# Sheet1.net
KiCad netlist of a schematic drawn in Altium Designer
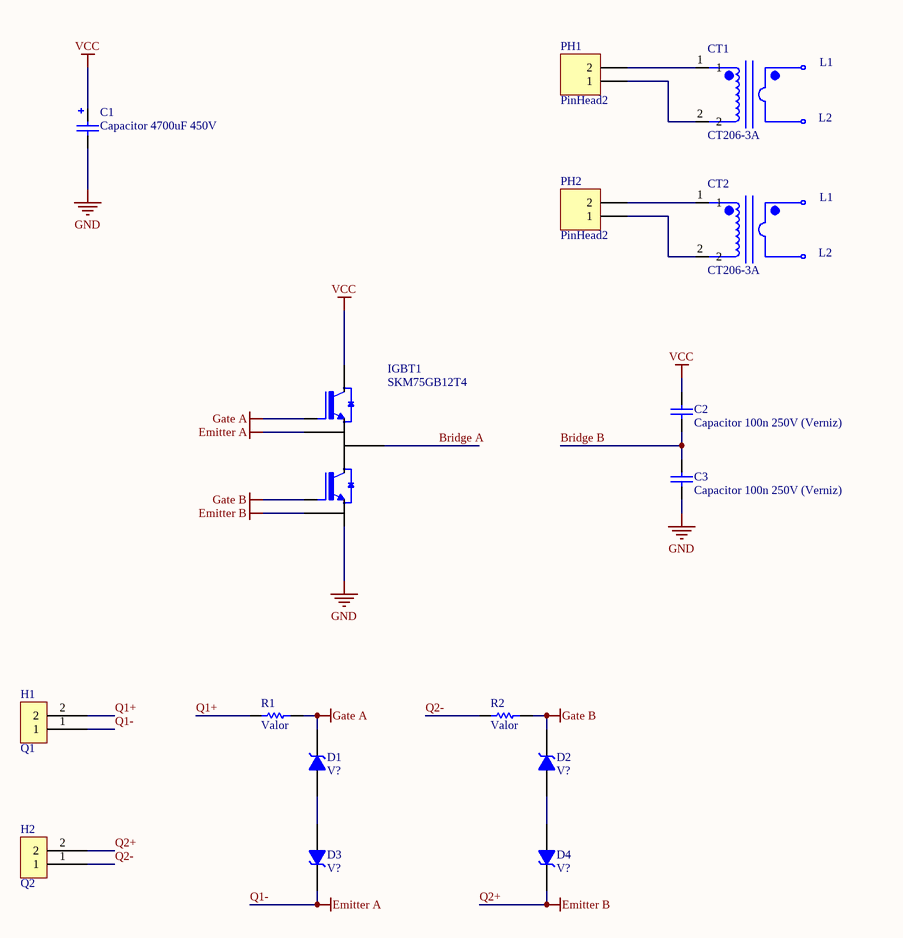
[diagram p0: Sheet1.SchDoc]

(export (version "E")
  (design (tool "Eeschema 10.0.6"))
  (components
    (comp (ref "C1")
      (value "Capacitor 4700uF 450V")
      (footprint "Capacitor 4700uF 450V RIFA")
      (libsource (lib "SPaivachlib1") (part "Capacitor 4700uF 450V"))
    )
    (comp (ref "C2")
      (value "Capacitor 100n 250V (Verniz)")
      (footprint "Capacitor 100n (cor verniz)")
      (libsource (lib "SPaivachlib1") (part "Capacitor 100n 250V (Verniz)"))
    )
    (comp (ref "C3")
      (value "Capacitor 100n 250V (Verniz)")
      (footprint "Capacitor 100n (cor verniz)")
      (libsource (lib "SPaivachlib1") (part "Capacitor 100n 250V (Verniz)"))
    )
    (comp (ref "CT1")
      (value "CT206-3A")
      (footprint "CT206-3A")
      (description "PTH Current Transformer")
      (libsource (lib "SPaivachlib1") (part "CT206-3A"))
    )
    (comp (ref "CT2")
      (value "CT206-3A")
      (footprint "CT206-3A")
      (description "PTH Current Transformer")
      (libsource (lib "SPaivachlib1") (part "CT206-3A"))
    )
    (comp (ref "D1")
      (value "V?")
      (footprint "SOD-80")
      (description "Diodo zener")
      (libsource (lib "LIB_Ampera_2021 (1)") (part "Zener"))
    )
    (comp (ref "D2")
      (value "V?")
      (footprint "SOD-80")
      (description "Diodo zener")
      (libsource (lib "LIB_Ampera_2021 (1)") (part "Zener"))
    )
    (comp (ref "D3")
      (value "V?")
      (footprint "SOD-80")
      (description "Diodo zener")
      (libsource (lib "LIB_Ampera_2021 (1)") (part "Zener"))
    )
    (comp (ref "D4")
      (value "V?")
      (footprint "SOD-80")
      (description "Diodo zener")
      (libsource (lib "LIB_Ampera_2021 (1)") (part "Zener"))
    )
    (comp (ref "H1")
      (value "Q1")
      (footprint "Pin Socket 1x2 TH Pitch 2.54mm")
      (description "Socket to header connector with 2 pins")
      (libsource (lib "LIB_Ampera_2021 (1)") (part "HEADER_SOCKET_2"))
    )
    (comp (ref "H2")
      (value "Q2")
      (footprint "Pin Socket 1x2 TH Pitch 2.54mm")
      (description "Socket to header connector with 2 pins")
      (libsource (lib "LIB_Ampera_2021 (1)") (part "HEADER_SOCKET_2"))
    )
    (comp (ref "IGBT1")
      (value "SKM75GB12T4")
      (footprint "SEMIKRON SKM75GB12T4")
      (libsource (lib "Schlib1") (part "SKM75GB12T4"))
    )
    (comp (ref "PH1")
      (value "PinHead2")
      (footprint "PinHead2")
      (libsource (lib "SPaivachlib1") (part "PinHead2"))
    )
    (comp (ref "PH2")
      (value "PinHead2")
      (footprint "PinHead2")
      (libsource (lib "SPaivachlib1") (part "PinHead2"))
    )
    (comp (ref "R1")
      (value "Valor")
      (footprint "RES_AXIAL_1W")
      (description "Resistor")
      (libsource (lib "LIB_Ampera_2021 (1)") (part "Resistor"))
    )
    (comp (ref "R2")
      (value "Valor")
      (footprint "RES_AXIAL_1W")
      (description "Resistor")
      (libsource (lib "LIB_Ampera_2021 (1)") (part "Resistor"))
    )
  )
  (nets
    (net (code "1") (name "/Bridge A") (class "Default")
      (node (ref "IGBT1") (pin "1") (pinfunction "E1_1") (pintype "passive"))
    )
    (net (code "2") (name "/Bridge B") (class "Default")
      (node (ref "C2") (pin "1") (pinfunction "1_1") (pintype "passive"))
      (node (ref "C3") (pin "2") (pinfunction "2_2") (pintype "passive"))
    )
    (net (code "3") (name "/Q1+") (class "Default")
      (node (ref "H1") (pin "2") (pinfunction "2_2") (pintype "passive"))
      (node (ref "R1") (pin "1") (pintype "passive"))
    )
    (net (code "4") (name "/Q2-") (class "Default")
      (node (ref "H2") (pin "1") (pinfunction "1_1") (pintype "passive"))
      (node (ref "R2") (pin "1") (pintype "passive"))
    )
    (net (code "5") (name "Emitter A") (class "Default")
      (node (ref "D3") (pin "K") (pinfunction "2_K") (pintype "passive"))
      (node (ref "H1") (pin "1") (pinfunction "1_1") (pintype "passive"))
      (node (ref "IGBT1") (pin "5") (pinfunction "E1_5") (pintype "passive"))
    )
    (net (code "6") (name "Emitter B") (class "Default")
      (node (ref "D4") (pin "K") (pinfunction "2_K") (pintype "passive"))
      (node (ref "H2") (pin "2") (pinfunction "2_2") (pintype "passive"))
      (node (ref "IGBT1") (pin "7") (pinfunction "E2_7") (pintype "passive"))
    )
    (net (code "7") (name "GND") (class "Default")
      (node (ref "C1") (pin "1") (pinfunction "1_1") (pintype "passive"))
      (node (ref "C3") (pin "1") (pinfunction "1_1") (pintype "passive"))
      (node (ref "IGBT1") (pin "2") (pinfunction "GND_2") (pintype "passive"))
    )
    (net (code "8") (name "Gate A") (class "Default")
      (node (ref "D1") (pin "K") (pinfunction "2_K") (pintype "passive"))
      (node (ref "IGBT1") (pin "4") (pinfunction "G1_4") (pintype "passive"))
      (node (ref "R1") (pin "2") (pintype "passive"))
    )
    (net (code "9") (name "Gate B") (class "Default")
      (node (ref "D2") (pin "K") (pinfunction "2_K") (pintype "passive"))
      (node (ref "IGBT1") (pin "6") (pinfunction "G2_6") (pintype "passive"))
      (node (ref "R2") (pin "2") (pintype "passive"))
    )
    (net (code "10") (name "Net-(CT1-Pad1)") (class "Default")
      (node (ref "CT1") (pin "1") (pinfunction "1_1") (pintype "passive"))
      (node (ref "PH1") (pin "2") (pinfunction "2_2") (pintype "passive"))
    )
    (net (code "11") (name "Net-(CT1-Pad2)") (class "Default")
      (node (ref "CT1") (pin "2") (pinfunction "2_2") (pintype "passive"))
      (node (ref "PH1") (pin "1") (pinfunction "1_1") (pintype "passive"))
    )
    (net (code "12") (name "Net-(CT2-Pad1)") (class "Default")
      (node (ref "CT2") (pin "1") (pinfunction "1_1") (pintype "passive"))
      (node (ref "PH2") (pin "2") (pinfunction "2_2") (pintype "passive"))
    )
    (net (code "13") (name "Net-(CT2-Pad2)") (class "Default")
      (node (ref "CT2") (pin "2") (pinfunction "2_2") (pintype "passive"))
      (node (ref "PH2") (pin "1") (pinfunction "1_1") (pintype "passive"))
    )
    (net (code "14") (name "Net-(D1-1)") (class "Default")
      (node (ref "D1") (pin "A") (pinfunction "1_A") (pintype "passive"))
      (node (ref "D3") (pin "A") (pinfunction "1_A") (pintype "passive"))
    )
    (net (code "15") (name "Net-(D2-1)") (class "Default")
      (node (ref "D2") (pin "A") (pinfunction "1_A") (pintype "passive"))
      (node (ref "D4") (pin "A") (pinfunction "1_A") (pintype "passive"))
    )
    (net (code "16") (name "VCC") (class "Default")
      (node (ref "C1") (pin "2") (pinfunction "2_2") (pintype "passive"))
      (node (ref "C2") (pin "2") (pinfunction "2_2") (pintype "passive"))
      (node (ref "IGBT1") (pin "3") (pinfunction "Vcc_3") (pintype "passive"))
    )
    (net (code "17") (name "unconnected-(IGBT1-C-Pad2)") (class "Default")
      (node (ref "IGBT1") (pin "2") (pinfunction "C_2") (pintype "passive"))
    )
    (net (code "18") (name "unconnected-(IGBT1-E-Pad3)") (class "Default")
      (node (ref "IGBT1") (pin "3") (pinfunction "E_3") (pintype "passive"))
    )
    (net (code "19") (name "unconnected-(IGBT1-E-Pad3)_1") (class "Default")
      (node (ref "IGBT1") (pin "3") (pinfunction "E_3") (pintype "passive"))
    )
  )
)
